# RH048_2.net
KiCad netlist of a schematic drawn in EAGLE
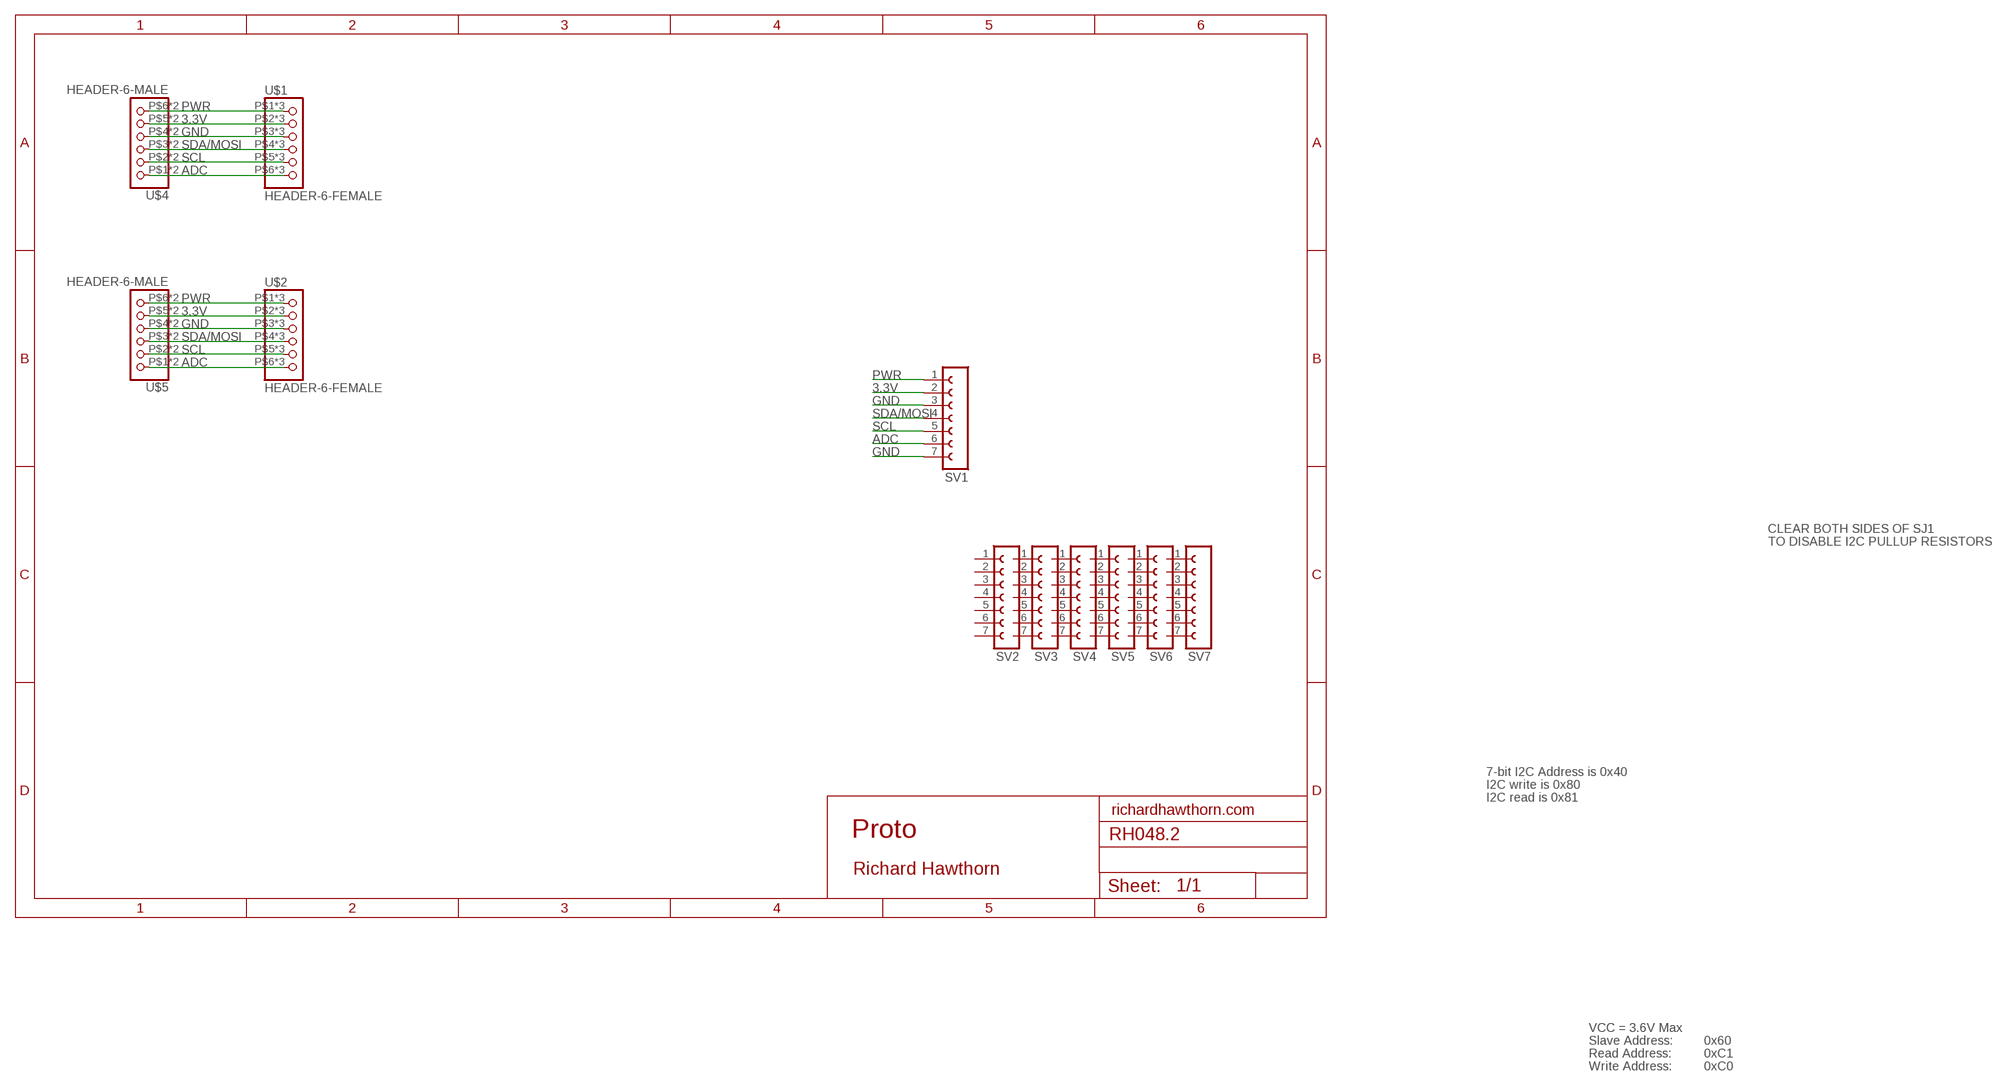
[diagram p0: schematic, sheet 1]

(export (version "E")
  (design (tool "Eeschema 10.0.6"))
  (components
    (comp (ref "SV1")
      (value "FE07-1")
      (footprint "eagle-import:FE07")
      (libsource (lib "eagle-import") (part "FE07-1"))
    )
    (comp (ref "SV2")
      (value "FE07-1")
      (footprint "eagle-import:FE07")
      (libsource (lib "eagle-import") (part "FE07-1"))
    )
    (comp (ref "SV3")
      (value "FE07-1")
      (footprint "eagle-import:FE07")
      (libsource (lib "eagle-import") (part "FE07-1"))
    )
    (comp (ref "SV4")
      (value "FE07-1")
      (footprint "eagle-import:FE07")
      (libsource (lib "eagle-import") (part "FE07-1"))
    )
    (comp (ref "SV5")
      (value "FE07-1")
      (footprint "eagle-import:FE07")
      (libsource (lib "eagle-import") (part "FE07-1"))
    )
    (comp (ref "SV6")
      (value "FE07-1")
      (footprint "eagle-import:FE07")
      (libsource (lib "eagle-import") (part "FE07-1"))
    )
    (comp (ref "SV7")
      (value "FE07-1")
      (footprint "eagle-import:FE07")
      (libsource (lib "eagle-import") (part "FE07-1"))
    )
    (comp (ref "U$1")
      (value "HEADER-6-FEMALE")
      (footprint "eagle-import:2MMHEADER6")
      (libsource (lib "eagle-import") (part "HEADER-6-FEMALE"))
    )
    (comp (ref "U$2")
      (value "HEADER-6-FEMALE")
      (footprint "eagle-import:2MMHEADER6")
      (libsource (lib "eagle-import") (part "HEADER-6-FEMALE"))
    )
    (comp (ref "U$4")
      (value "HEADER-6-MALE")
      (footprint "eagle-import:2MMHEADERPIN6")
      (libsource (lib "eagle-import") (part "HEADER-6-MALE"))
    )
    (comp (ref "U$5")
      (value "HEADER-6-MALE")
      (footprint "eagle-import:2MMHEADERPIN6")
      (libsource (lib "eagle-import") (part "HEADER-6-MALE"))
    )
  )
  (nets
    (net (code "1") (name "/3.3V") (class "Default")
      (node (ref "SV1") (pin "2") (pinfunction "2_2") (pintype "passive"))
      (node (ref "U$1") (pin "P$10") (pinfunction "2_P$10") (pintype "passive"))
      (node (ref "U$1") (pin "P$18") (pinfunction "2_P$18") (pintype "passive"))
      (node (ref "U$1") (pin "P$2") (pinfunction "2_P$2") (pintype "passive"))
      (node (ref "U$2") (pin "P$10") (pinfunction "2_P$10") (pintype "passive"))
      (node (ref "U$2") (pin "P$18") (pinfunction "2_P$18") (pintype "passive"))
      (node (ref "U$2") (pin "P$2") (pinfunction "2_P$2") (pintype "passive"))
      (node (ref "U$4") (pin "P$13") (pinfunction "5_P$13") (pintype "passive"))
      (node (ref "U$4") (pin "P$5") (pinfunction "5_P$5") (pintype "passive"))
      (node (ref "U$5") (pin "P$13") (pinfunction "5_P$13") (pintype "passive"))
      (node (ref "U$5") (pin "P$5") (pinfunction "5_P$5") (pintype "passive"))
    )
    (net (code "2") (name "/ADC") (class "Default")
      (node (ref "SV1") (pin "6") (pinfunction "6_6") (pintype "passive"))
      (node (ref "U$1") (pin "P$14") (pinfunction "6_P$14") (pintype "passive"))
      (node (ref "U$1") (pin "P$22") (pinfunction "6_P$22") (pintype "passive"))
      (node (ref "U$1") (pin "P$6") (pinfunction "6_P$6") (pintype "passive"))
      (node (ref "U$2") (pin "P$14") (pinfunction "6_P$14") (pintype "passive"))
      (node (ref "U$2") (pin "P$22") (pinfunction "6_P$22") (pintype "passive"))
      (node (ref "U$2") (pin "P$6") (pinfunction "6_P$6") (pintype "passive"))
      (node (ref "U$4") (pin "P$1") (pinfunction "1_P$1") (pintype "passive"))
      (node (ref "U$4") (pin "P$9") (pinfunction "1_P$9") (pintype "passive"))
      (node (ref "U$5") (pin "P$1") (pinfunction "1_P$1") (pintype "passive"))
      (node (ref "U$5") (pin "P$9") (pinfunction "1_P$9") (pintype "passive"))
    )
    (net (code "3") (name "/GND") (class "Default")
      (node (ref "SV1") (pin "3") (pinfunction "3_3") (pintype "passive"))
      (node (ref "SV1") (pin "7") (pinfunction "7_7") (pintype "passive"))
      (node (ref "U$1") (pin "P$11") (pinfunction "3_P$11") (pintype "passive"))
      (node (ref "U$1") (pin "P$19") (pinfunction "3_P$19") (pintype "passive"))
      (node (ref "U$1") (pin "P$3") (pinfunction "3_P$3") (pintype "passive"))
      (node (ref "U$2") (pin "P$11") (pinfunction "3_P$11") (pintype "passive"))
      (node (ref "U$2") (pin "P$19") (pinfunction "3_P$19") (pintype "passive"))
      (node (ref "U$2") (pin "P$3") (pinfunction "3_P$3") (pintype "passive"))
      (node (ref "U$4") (pin "P$12") (pinfunction "4_P$12") (pintype "passive"))
      (node (ref "U$4") (pin "P$4") (pinfunction "4_P$4") (pintype "passive"))
      (node (ref "U$5") (pin "P$12") (pinfunction "4_P$12") (pintype "passive"))
      (node (ref "U$5") (pin "P$4") (pinfunction "4_P$4") (pintype "passive"))
    )
    (net (code "4") (name "/PWR") (class "Default")
      (node (ref "SV1") (pin "1") (pinfunction "1_1") (pintype "passive"))
      (node (ref "U$1") (pin "P$1") (pinfunction "1_P$1") (pintype "passive"))
      (node (ref "U$1") (pin "P$17") (pinfunction "1_P$17") (pintype "passive"))
      (node (ref "U$1") (pin "P$9") (pinfunction "1_P$9") (pintype "passive"))
      (node (ref "U$2") (pin "P$1") (pinfunction "1_P$1") (pintype "passive"))
      (node (ref "U$2") (pin "P$17") (pinfunction "1_P$17") (pintype "passive"))
      (node (ref "U$2") (pin "P$9") (pinfunction "1_P$9") (pintype "passive"))
      (node (ref "U$4") (pin "P$14") (pinfunction "6_P$14") (pintype "passive"))
      (node (ref "U$4") (pin "P$6") (pinfunction "6_P$6") (pintype "passive"))
      (node (ref "U$5") (pin "P$14") (pinfunction "6_P$14") (pintype "passive"))
      (node (ref "U$5") (pin "P$6") (pinfunction "6_P$6") (pintype "passive"))
    )
    (net (code "5") (name "/SCL") (class "Default")
      (node (ref "SV1") (pin "5") (pinfunction "5_5") (pintype "passive"))
      (node (ref "U$1") (pin "P$13") (pinfunction "5_P$13") (pintype "passive"))
      (node (ref "U$1") (pin "P$21") (pinfunction "5_P$21") (pintype "passive"))
      (node (ref "U$1") (pin "P$5") (pinfunction "5_P$5") (pintype "passive"))
      (node (ref "U$2") (pin "P$13") (pinfunction "5_P$13") (pintype "passive"))
      (node (ref "U$2") (pin "P$21") (pinfunction "5_P$21") (pintype "passive"))
      (node (ref "U$2") (pin "P$5") (pinfunction "5_P$5") (pintype "passive"))
      (node (ref "U$4") (pin "P$10") (pinfunction "2_P$10") (pintype "passive"))
      (node (ref "U$4") (pin "P$2") (pinfunction "2_P$2") (pintype "passive"))
      (node (ref "U$5") (pin "P$10") (pinfunction "2_P$10") (pintype "passive"))
      (node (ref "U$5") (pin "P$2") (pinfunction "2_P$2") (pintype "passive"))
    )
    (net (code "6") (name "/SDA{slash}MOSI") (class "Default")
      (node (ref "SV1") (pin "4") (pinfunction "4_4") (pintype "passive"))
      (node (ref "U$1") (pin "P$12") (pinfunction "4_P$12") (pintype "passive"))
      (node (ref "U$1") (pin "P$20") (pinfunction "4_P$20") (pintype "passive"))
      (node (ref "U$1") (pin "P$4") (pinfunction "4_P$4") (pintype "passive"))
      (node (ref "U$2") (pin "P$12") (pinfunction "4_P$12") (pintype "passive"))
      (node (ref "U$2") (pin "P$20") (pinfunction "4_P$20") (pintype "passive"))
      (node (ref "U$2") (pin "P$4") (pinfunction "4_P$4") (pintype "passive"))
      (node (ref "U$4") (pin "P$11") (pinfunction "3_P$11") (pintype "passive"))
      (node (ref "U$4") (pin "P$3") (pinfunction "3_P$3") (pintype "passive"))
      (node (ref "U$5") (pin "P$11") (pinfunction "3_P$11") (pintype "passive"))
      (node (ref "U$5") (pin "P$3") (pinfunction "3_P$3") (pintype "passive"))
    )
    (net (code "7") (name "unconnected-(SV2-Pad1)") (class "Default")
      (node (ref "SV2") (pin "1") (pinfunction "1_1") (pintype "passive"))
    )
    (net (code "8") (name "unconnected-(SV2-Pad2)") (class "Default")
      (node (ref "SV2") (pin "2") (pinfunction "2_2") (pintype "passive"))
    )
    (net (code "9") (name "unconnected-(SV2-Pad3)") (class "Default")
      (node (ref "SV2") (pin "3") (pinfunction "3_3") (pintype "passive"))
    )
    (net (code "10") (name "unconnected-(SV2-Pad4)") (class "Default")
      (node (ref "SV2") (pin "4") (pinfunction "4_4") (pintype "passive"))
    )
    (net (code "11") (name "unconnected-(SV2-Pad5)") (class "Default")
      (node (ref "SV2") (pin "5") (pinfunction "5_5") (pintype "passive"))
    )
    (net (code "12") (name "unconnected-(SV2-Pad6)") (class "Default")
      (node (ref "SV2") (pin "6") (pinfunction "6_6") (pintype "passive"))
    )
    (net (code "13") (name "unconnected-(SV2-Pad7)") (class "Default")
      (node (ref "SV2") (pin "7") (pinfunction "7_7") (pintype "passive"))
    )
    (net (code "14") (name "unconnected-(SV3-Pad1)") (class "Default")
      (node (ref "SV3") (pin "1") (pinfunction "1_1") (pintype "passive"))
    )
    (net (code "15") (name "unconnected-(SV3-Pad2)") (class "Default")
      (node (ref "SV3") (pin "2") (pinfunction "2_2") (pintype "passive"))
    )
    (net (code "16") (name "unconnected-(SV3-Pad3)") (class "Default")
      (node (ref "SV3") (pin "3") (pinfunction "3_3") (pintype "passive"))
    )
    (net (code "17") (name "unconnected-(SV3-Pad4)") (class "Default")
      (node (ref "SV3") (pin "4") (pinfunction "4_4") (pintype "passive"))
    )
    (net (code "18") (name "unconnected-(SV3-Pad5)") (class "Default")
      (node (ref "SV3") (pin "5") (pinfunction "5_5") (pintype "passive"))
    )
    (net (code "19") (name "unconnected-(SV3-Pad6)") (class "Default")
      (node (ref "SV3") (pin "6") (pinfunction "6_6") (pintype "passive"))
    )
    (net (code "20") (name "unconnected-(SV3-Pad7)") (class "Default")
      (node (ref "SV3") (pin "7") (pinfunction "7_7") (pintype "passive"))
    )
    (net (code "21") (name "unconnected-(SV4-Pad1)") (class "Default")
      (node (ref "SV4") (pin "1") (pinfunction "1_1") (pintype "passive"))
    )
    (net (code "22") (name "unconnected-(SV4-Pad2)") (class "Default")
      (node (ref "SV4") (pin "2") (pinfunction "2_2") (pintype "passive"))
    )
    (net (code "23") (name "unconnected-(SV4-Pad3)") (class "Default")
      (node (ref "SV4") (pin "3") (pinfunction "3_3") (pintype "passive"))
    )
    (net (code "24") (name "unconnected-(SV4-Pad4)") (class "Default")
      (node (ref "SV4") (pin "4") (pinfunction "4_4") (pintype "passive"))
    )
    (net (code "25") (name "unconnected-(SV4-Pad5)") (class "Default")
      (node (ref "SV4") (pin "5") (pinfunction "5_5") (pintype "passive"))
    )
    (net (code "26") (name "unconnected-(SV4-Pad6)") (class "Default")
      (node (ref "SV4") (pin "6") (pinfunction "6_6") (pintype "passive"))
    )
    (net (code "27") (name "unconnected-(SV4-Pad7)") (class "Default")
      (node (ref "SV4") (pin "7") (pinfunction "7_7") (pintype "passive"))
    )
    (net (code "28") (name "unconnected-(SV5-Pad1)") (class "Default")
      (node (ref "SV5") (pin "1") (pinfunction "1_1") (pintype "passive"))
    )
    (net (code "29") (name "unconnected-(SV5-Pad2)") (class "Default")
      (node (ref "SV5") (pin "2") (pinfunction "2_2") (pintype "passive"))
    )
    (net (code "30") (name "unconnected-(SV5-Pad3)") (class "Default")
      (node (ref "SV5") (pin "3") (pinfunction "3_3") (pintype "passive"))
    )
    (net (code "31") (name "unconnected-(SV5-Pad4)") (class "Default")
      (node (ref "SV5") (pin "4") (pinfunction "4_4") (pintype "passive"))
    )
    (net (code "32") (name "unconnected-(SV5-Pad5)") (class "Default")
      (node (ref "SV5") (pin "5") (pinfunction "5_5") (pintype "passive"))
    )
    (net (code "33") (name "unconnected-(SV5-Pad6)") (class "Default")
      (node (ref "SV5") (pin "6") (pinfunction "6_6") (pintype "passive"))
    )
    (net (code "34") (name "unconnected-(SV5-Pad7)") (class "Default")
      (node (ref "SV5") (pin "7") (pinfunction "7_7") (pintype "passive"))
    )
    (net (code "35") (name "unconnected-(SV6-Pad1)") (class "Default")
      (node (ref "SV6") (pin "1") (pinfunction "1_1") (pintype "passive"))
    )
    (net (code "36") (name "unconnected-(SV6-Pad2)") (class "Default")
      (node (ref "SV6") (pin "2") (pinfunction "2_2") (pintype "passive"))
    )
    (net (code "37") (name "unconnected-(SV6-Pad3)") (class "Default")
      (node (ref "SV6") (pin "3") (pinfunction "3_3") (pintype "passive"))
    )
    (net (code "38") (name "unconnected-(SV6-Pad4)") (class "Default")
      (node (ref "SV6") (pin "4") (pinfunction "4_4") (pintype "passive"))
    )
    (net (code "39") (name "unconnected-(SV6-Pad5)") (class "Default")
      (node (ref "SV6") (pin "5") (pinfunction "5_5") (pintype "passive"))
    )
    (net (code "40") (name "unconnected-(SV6-Pad6)") (class "Default")
      (node (ref "SV6") (pin "6") (pinfunction "6_6") (pintype "passive"))
    )
    (net (code "41") (name "unconnected-(SV6-Pad7)") (class "Default")
      (node (ref "SV6") (pin "7") (pinfunction "7_7") (pintype "passive"))
    )
    (net (code "42") (name "unconnected-(SV7-Pad1)") (class "Default")
      (node (ref "SV7") (pin "1") (pinfunction "1_1") (pintype "passive"))
    )
    (net (code "43") (name "unconnected-(SV7-Pad2)") (class "Default")
      (node (ref "SV7") (pin "2") (pinfunction "2_2") (pintype "passive"))
    )
    (net (code "44") (name "unconnected-(SV7-Pad3)") (class "Default")
      (node (ref "SV7") (pin "3") (pinfunction "3_3") (pintype "passive"))
    )
    (net (code "45") (name "unconnected-(SV7-Pad4)") (class "Default")
      (node (ref "SV7") (pin "4") (pinfunction "4_4") (pintype "passive"))
    )
    (net (code "46") (name "unconnected-(SV7-Pad5)") (class "Default")
      (node (ref "SV7") (pin "5") (pinfunction "5_5") (pintype "passive"))
    )
    (net (code "47") (name "unconnected-(SV7-Pad6)") (class "Default")
      (node (ref "SV7") (pin "6") (pinfunction "6_6") (pintype "passive"))
    )
    (net (code "48") (name "unconnected-(SV7-Pad7)") (class "Default")
      (node (ref "SV7") (pin "7") (pinfunction "7_7") (pintype "passive"))
    )
  )
)
